# SparkFun_Color_Sensor_OPT4048.net
KiCad netlist of a schematic drawn in EAGLE
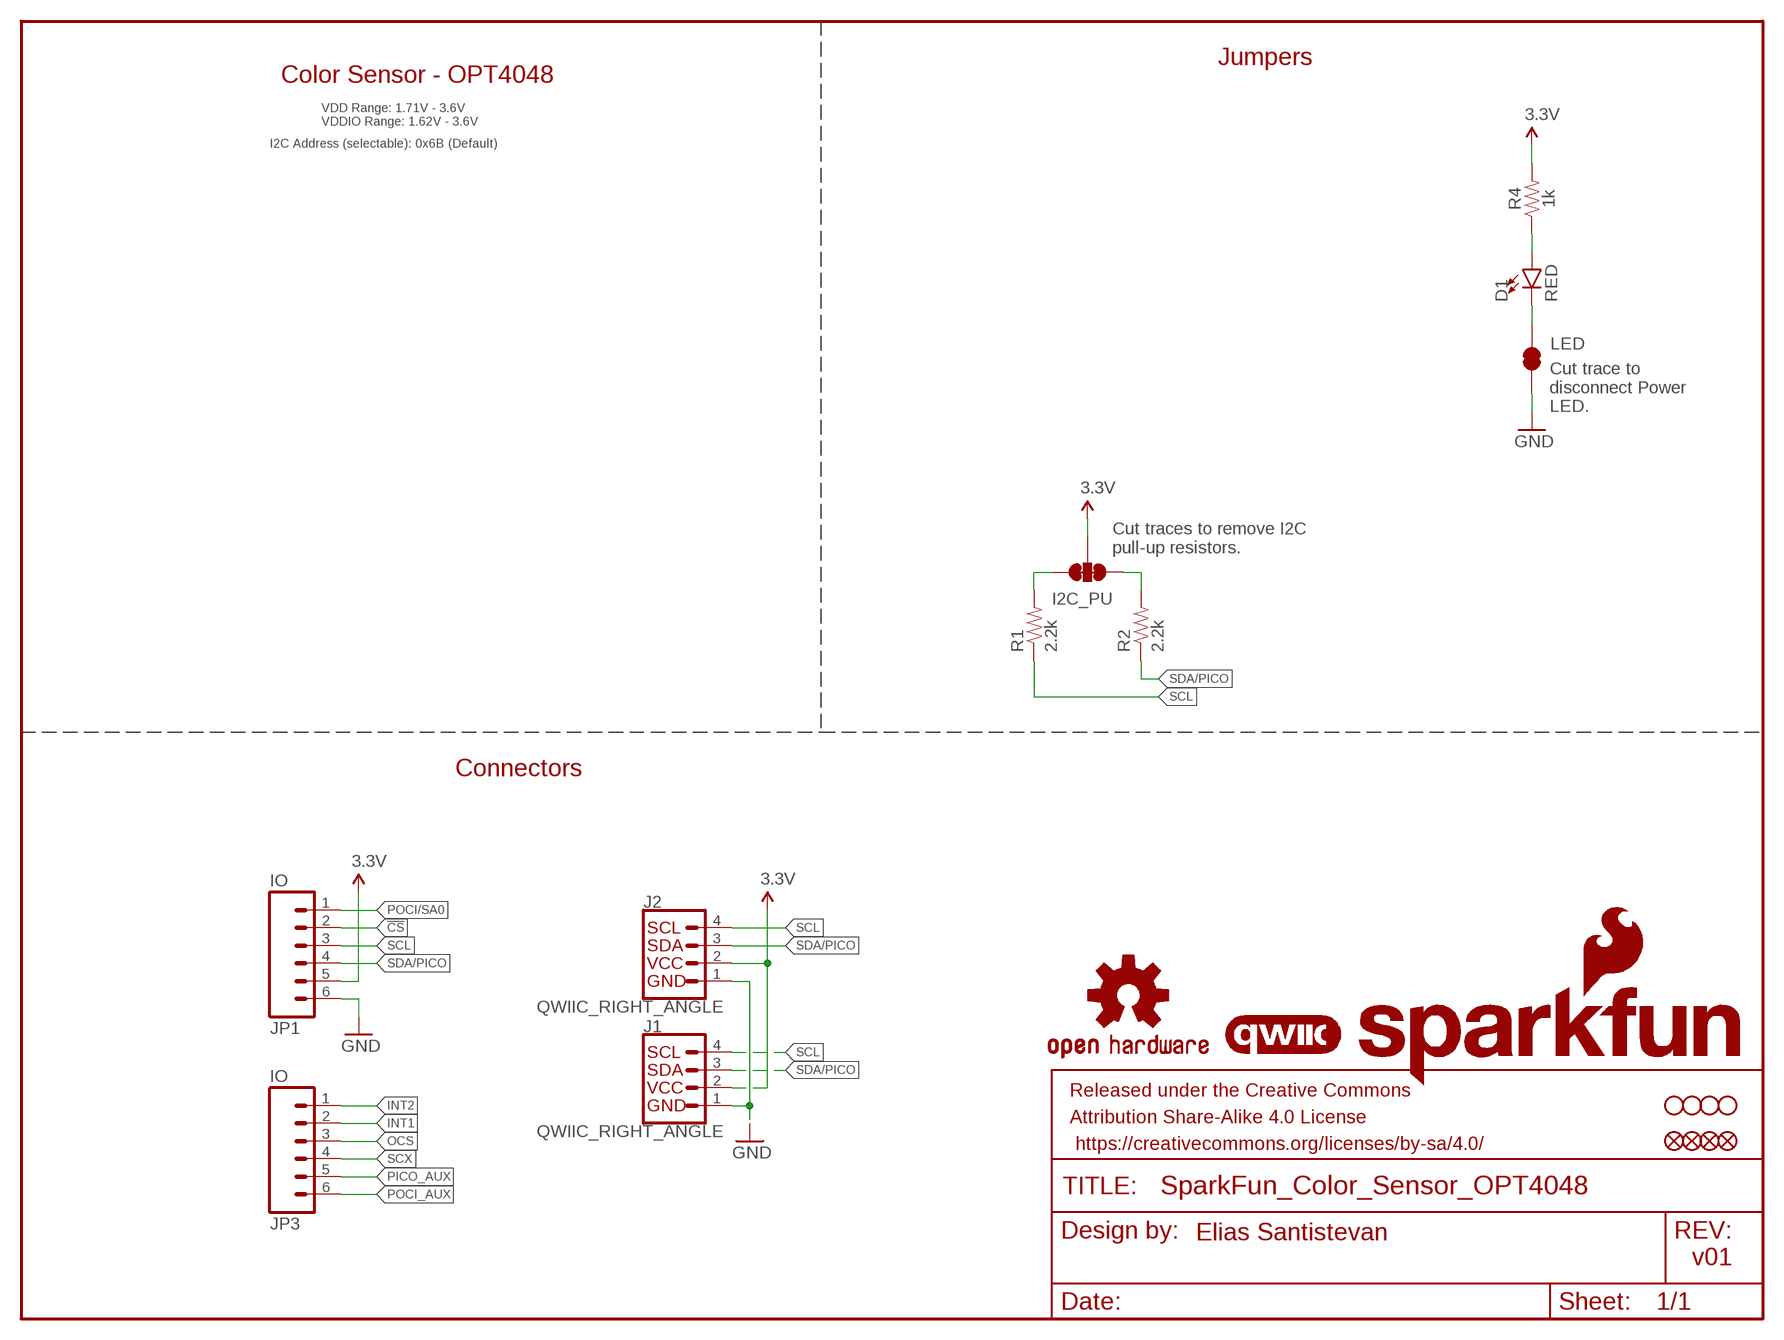
[diagram p0: schematic, sheet 1]

(export (version "E")
  (design (tool "Eeschema 10.0.6"))
  (components
    (comp (ref "D1")
      (value "RED")
      (footprint "eagle-import:LED-0603")
      (libsource (lib "eagle-import") (part "LED-RED0603"))
    )
    (comp (ref "FD1")
      (value "FIDUCIALUFIDUCIAL")
      (footprint "eagle-import:FIDUCIAL-MICRO")
      (libsource (lib "eagle-import") (part "FIDUCIALUFIDUCIAL"))
    )
    (comp (ref "FD2")
      (value "FIDUCIALUFIDUCIAL")
      (footprint "eagle-import:FIDUCIAL-MICRO")
      (libsource (lib "eagle-import") (part "FIDUCIALUFIDUCIAL"))
    )
    (comp (ref "FID1")
      (value "FIDUCIALUFIDUCIAL")
      (footprint "eagle-import:FIDUCIAL-MICRO")
      (libsource (lib "eagle-import") (part "FIDUCIALUFIDUCIAL"))
    )
    (comp (ref "FID2")
      (value "FIDUCIALUFIDUCIAL")
      (footprint "eagle-import:FIDUCIAL-MICRO")
      (libsource (lib "eagle-import") (part "FIDUCIALUFIDUCIAL"))
    )
    (comp (ref "FRAME1")
      (value "FRAME-LETTER")
      (footprint "eagle-import:CREATIVE_COMMONS")
      (fields (field (name "DESIGNER") "Elias Santistevan"))
      (libsource (lib "eagle-import") (part "FRAME-LETTER"))
    )
    (comp (ref "I2C_PU")
      (value "S_MODE")
      (footprint "eagle-import:SMT-JUMPER_3_2-NC_TRACE_SILK")
      (libsource (lib "eagle-import") (part "JUMPER-SMT_3_2-NC_TRACE_SILK"))
    )
    (comp (ref "J1")
      (value "QWIIC_RIGHT_ANGLE")
      (footprint "eagle-import:JST04_1MM_RA")
      (libsource (lib "eagle-import") (part "QWIIC_CONNECTORJS-1MM"))
    )
    (comp (ref "J2")
      (value "QWIIC_RIGHT_ANGLE")
      (footprint "eagle-import:JST04_1MM_RA")
      (libsource (lib "eagle-import") (part "QWIIC_CONNECTORJS-1MM"))
    )
    (comp (ref "JP1")
      (value "IO")
      (footprint "eagle-import:1X06_NO_SILK")
      (libsource (lib "eagle-import") (part "CONN_06NO_SILK_NO_POP"))
    )
    (comp (ref "JP3")
      (value "IO")
      (footprint "eagle-import:1X06_NO_SILK")
      (libsource (lib "eagle-import") (part "CONN_06NO_SILK_NO_POP"))
    )
    (comp (ref "LED")
      (value "JUMPER-SMT_2_NC_TRACE_SILK")
      (footprint "eagle-import:SMT-JUMPER_2_NC_TRACE_SILK")
      (libsource (lib "eagle-import") (part "JUMPER-SMT_2_NC_TRACE_SILK"))
    )
    (comp (ref "LOGO1")
      (value "QWIIC_LOGO_4MM")
      (footprint "eagle-import:QWIIC_4MM")
      (libsource (lib "eagle-import") (part "QWIIC_LOGO_4MM"))
    )
    (comp (ref "LOGO2")
      (value "OSHW-LOGOMINI")
      (footprint "eagle-import:OSHW-LOGO-MINI")
      (libsource (lib "eagle-import") (part "OSHW-LOGOMINI"))
    )
    (comp (ref "LOGO3")
      (value "SFE_LOGO_NAME_FLAME.1_INCH")
      (footprint "eagle-import:SFE_LOGO_NAME_FLAME_.1")
      (libsource (lib "eagle-import") (part "SFE_LOGO_NAME_FLAME.1_INCH"))
    )
    (comp (ref "R1")
      (value "2.2k")
      (footprint "eagle-import:0603")
      (libsource (lib "eagle-import") (part "2.2KOHM-0603-1/10W-1%"))
    )
    (comp (ref "R2")
      (value "2.2k")
      (footprint "eagle-import:0603")
      (libsource (lib "eagle-import") (part "2.2KOHM-0603-1/10W-1%"))
    )
    (comp (ref "R4")
      (value "1k")
      (footprint "eagle-import:0603")
      (libsource (lib "eagle-import") (part "1KOHM-0603-1/10W-1%"))
    )
    (comp (ref "STANDOFF1")
      (value "STAND-OFFTIGHT")
      (footprint "eagle-import:STAND-OFF-TIGHT")
      (libsource (lib "eagle-import") (part "STAND-OFFTIGHT"))
    )
    (comp (ref "STANDOFF2")
      (value "STAND-OFFTIGHT")
      (footprint "eagle-import:STAND-OFF-TIGHT")
      (libsource (lib "eagle-import") (part "STAND-OFFTIGHT"))
    )
    (comp (ref "STANDOFF3")
      (value "STAND-OFFTIGHT")
      (footprint "eagle-import:STAND-OFF-TIGHT")
      (libsource (lib "eagle-import") (part "STAND-OFFTIGHT"))
    )
    (comp (ref "STANDOFF4")
      (value "STAND-OFFTIGHT")
      (footprint "eagle-import:STAND-OFF-TIGHT")
      (libsource (lib "eagle-import") (part "STAND-OFFTIGHT"))
    )
  )
  (nets
    (net (code "1") (name "/~{CS}") (class "Default")
      (node (ref "JP1") (pin "2") (pinfunction "2_2") (pintype "passive"))
    )
    (net (code "2") (name "3.3V") (class "Default")
      (node (ref "I2C_PU") (pin "2") (pinfunction "2_2") (pintype "passive"))
      (node (ref "J1") (pin "2") (pinfunction "2_2") (pintype "power_in"))
      (node (ref "J2") (pin "2") (pinfunction "2_2") (pintype "power_in"))
      (node (ref "JP1") (pin "5") (pinfunction "5_5") (pintype "passive"))
      (node (ref "R4") (pin "2") (pinfunction "2_2") (pintype "passive"))
    )
    (net (code "3") (name "GND") (class "Default")
      (node (ref "J1") (pin "1") (pinfunction "1_1") (pintype "power_in"))
      (node (ref "J2") (pin "1") (pinfunction "1_1") (pintype "power_in"))
      (node (ref "JP1") (pin "6") (pinfunction "6_6") (pintype "passive"))
      (node (ref "LED") (pin "1") (pinfunction "1_1") (pintype "passive"))
    )
    (net (code "4") (name "INT1") (class "Default")
      (node (ref "JP3") (pin "2") (pinfunction "2_2") (pintype "passive"))
    )
    (net (code "5") (name "INT2") (class "Default")
      (node (ref "JP3") (pin "1") (pinfunction "1_1") (pintype "passive"))
    )
    (net (code "6") (name "Net-(D1-PadA)") (class "Default")
      (node (ref "D1") (pin "A") (pinfunction "A_A") (pintype "passive"))
      (node (ref "R4") (pin "1") (pinfunction "1_1") (pintype "passive"))
    )
    (net (code "7") (name "Net-(D1-PadC)") (class "Default")
      (node (ref "D1") (pin "C") (pinfunction "C_C") (pintype "passive"))
      (node (ref "LED") (pin "2") (pinfunction "2_2") (pintype "passive"))
    )
    (net (code "8") (name "Net-(I2C_PU-Pad1)") (class "Default")
      (node (ref "I2C_PU") (pin "1") (pinfunction "1_1") (pintype "passive"))
      (node (ref "R1") (pin "2") (pinfunction "2_2") (pintype "passive"))
    )
    (net (code "9") (name "Net-(I2C_PU-Pad3)") (class "Default")
      (node (ref "I2C_PU") (pin "3") (pinfunction "3_3") (pintype "passive"))
      (node (ref "R2") (pin "2") (pinfunction "2_2") (pintype "passive"))
    )
    (net (code "10") (name "OCS") (class "Default")
      (node (ref "JP3") (pin "3") (pinfunction "3_3") (pintype "passive"))
    )
    (net (code "11") (name "PICO_AUX") (class "Default")
      (node (ref "JP3") (pin "5") (pinfunction "5_5") (pintype "passive"))
    )
    (net (code "12") (name "POCI_AUX") (class "Default")
      (node (ref "JP3") (pin "6") (pinfunction "6_6") (pintype "passive"))
    )
    (net (code "13") (name "POCI{slash}SA0") (class "Default")
      (node (ref "JP1") (pin "1") (pinfunction "1_1") (pintype "passive"))
    )
    (net (code "14") (name "SCL") (class "Default")
      (node (ref "J1") (pin "4") (pinfunction "4_4") (pintype "passive"))
      (node (ref "J2") (pin "4") (pinfunction "4_4") (pintype "passive"))
      (node (ref "JP1") (pin "3") (pinfunction "3_3") (pintype "passive"))
      (node (ref "R1") (pin "1") (pinfunction "1_1") (pintype "passive"))
    )
    (net (code "15") (name "SCX") (class "Default")
      (node (ref "JP3") (pin "4") (pinfunction "4_4") (pintype "passive"))
    )
    (net (code "16") (name "SDA{slash}PICO") (class "Default")
      (node (ref "J1") (pin "3") (pinfunction "3_3") (pintype "passive"))
      (node (ref "J2") (pin "3") (pinfunction "3_3") (pintype "passive"))
      (node (ref "JP1") (pin "4") (pinfunction "4_4") (pintype "passive"))
      (node (ref "R2") (pin "1") (pinfunction "1_1") (pintype "passive"))
    )
  )
)
